# dual_pol_balun_multilayer.net
KiCad netlist of a schematic drawn in EAGLE
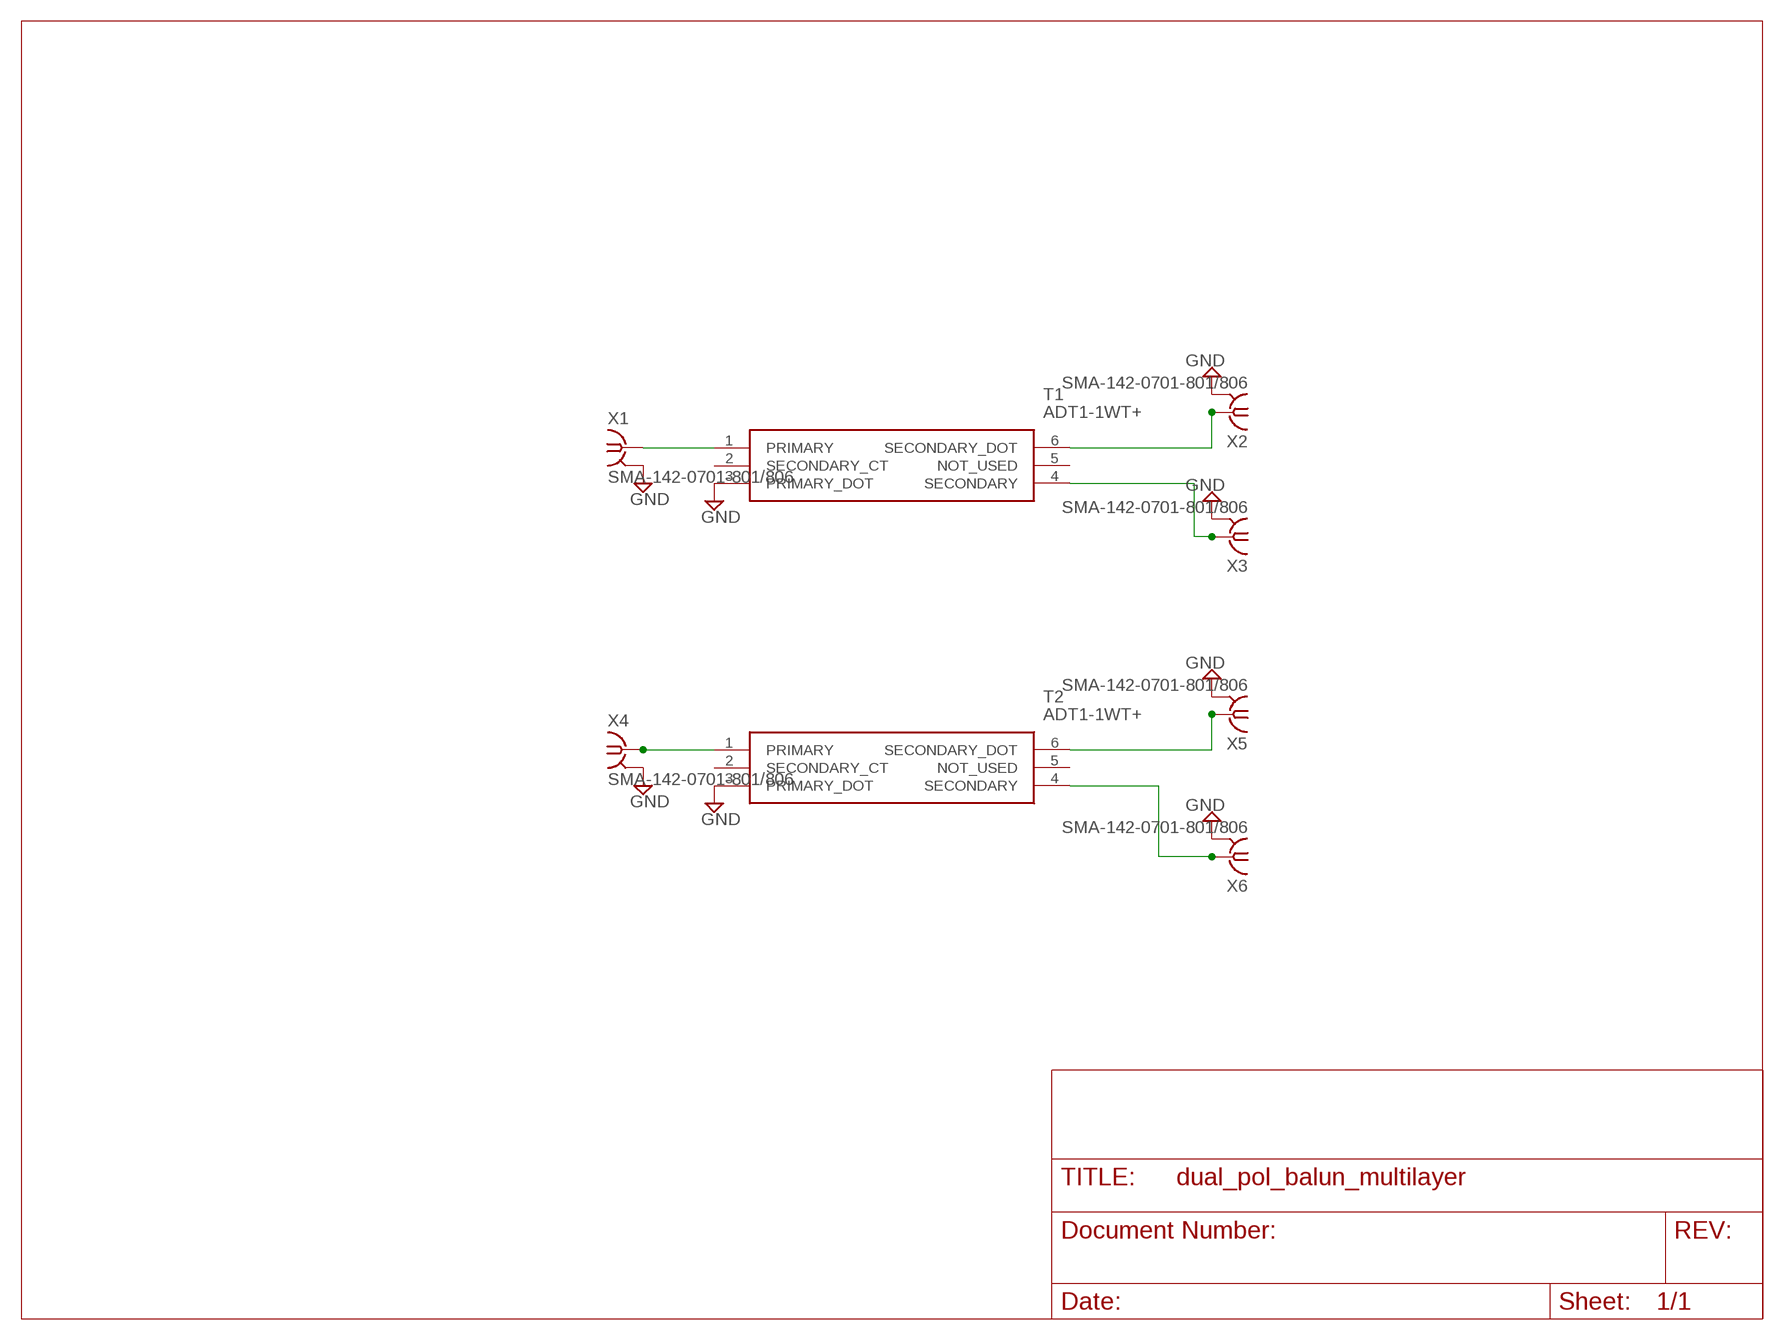
[diagram p0: schematic, sheet 1]

(export (version "E")
  (design (tool "Eeschema 10.0.6"))
  (components
    (comp (ref "T1")
      (value "ADT1-1WT+")
      (footprint "eagle-import:ADT11WT")
      (fields (field (name "MOUSER_PART_NUMBER") "139-ADT1-1WT"))
      (libsource (lib "eagle-import") (part "ADT1-1WT+"))
    )
    (comp (ref "T2")
      (value "ADT1-1WT+")
      (footprint "eagle-import:ADT11WT")
      (fields (field (name "MOUSER_PART_NUMBER") "139-ADT1-1WT"))
      (libsource (lib "eagle-import") (part "ADT1-1WT+"))
    )
    (comp (ref "X1")
      (value "SMA-142-0701-801/806")
      (footprint "eagle-import:J502-ND-142-0701-801_806")
      (fields (field (name "MF") "JOHNSON COMPONENTS") (field (name "MPN") "142-0701-801"))
      (libsource (lib "eagle-import") (part "SMA-142-0701-801/806"))
    )
    (comp (ref "X2")
      (value "SMA-142-0701-801/806")
      (footprint "eagle-import:J502-ND-142-0701-801_806")
      (fields (field (name "MF") "JOHNSON COMPONENTS") (field (name "MPN") "142-0701-801"))
      (libsource (lib "eagle-import") (part "SMA-142-0701-801/806"))
    )
    (comp (ref "X3")
      (value "SMA-142-0701-801/806")
      (footprint "eagle-import:J502-ND-142-0701-801_806")
      (fields (field (name "MF") "JOHNSON COMPONENTS") (field (name "MPN") "142-0701-801"))
      (libsource (lib "eagle-import") (part "SMA-142-0701-801/806"))
    )
    (comp (ref "X4")
      (value "SMA-142-0701-801/806")
      (footprint "eagle-import:J502-ND-142-0701-801_806")
      (fields (field (name "MF") "JOHNSON COMPONENTS") (field (name "MPN") "142-0701-801"))
      (libsource (lib "eagle-import") (part "SMA-142-0701-801/806"))
    )
    (comp (ref "X5")
      (value "SMA-142-0701-801/806")
      (footprint "eagle-import:J502-ND-142-0701-801_806")
      (fields (field (name "MF") "JOHNSON COMPONENTS") (field (name "MPN") "142-0701-801"))
      (libsource (lib "eagle-import") (part "SMA-142-0701-801/806"))
    )
    (comp (ref "X6")
      (value "SMA-142-0701-801/806")
      (footprint "eagle-import:J502-ND-142-0701-801_806")
      (fields (field (name "MF") "JOHNSON COMPONENTS") (field (name "MPN") "142-0701-801"))
      (libsource (lib "eagle-import") (part "SMA-142-0701-801/806"))
    )
  )
  (nets
    (net (code "1") (name "GND") (class "Default")
      (node (ref "T1") (pin "3") (pinfunction "PRIMARY_DOT_3") (pintype "bidirectional"))
      (node (ref "T2") (pin "3") (pinfunction "PRIMARY_DOT_3") (pintype "bidirectional"))
      (node (ref "X1") (pin "G@1") (pinfunction "2_G@1") (pintype "passive"))
      (node (ref "X1") (pin "G@2") (pinfunction "2_G@2") (pintype "passive"))
      (node (ref "X1") (pin "G@3") (pinfunction "2_G@3") (pintype "passive"))
      (node (ref "X1") (pin "G@4") (pinfunction "2_G@4") (pintype "passive"))
      (node (ref "X2") (pin "G@1") (pinfunction "2_G@1") (pintype "passive"))
      (node (ref "X2") (pin "G@2") (pinfunction "2_G@2") (pintype "passive"))
      (node (ref "X2") (pin "G@3") (pinfunction "2_G@3") (pintype "passive"))
      (node (ref "X2") (pin "G@4") (pinfunction "2_G@4") (pintype "passive"))
      (node (ref "X3") (pin "G@1") (pinfunction "2_G@1") (pintype "passive"))
      (node (ref "X3") (pin "G@2") (pinfunction "2_G@2") (pintype "passive"))
      (node (ref "X3") (pin "G@3") (pinfunction "2_G@3") (pintype "passive"))
      (node (ref "X3") (pin "G@4") (pinfunction "2_G@4") (pintype "passive"))
      (node (ref "X4") (pin "G@1") (pinfunction "2_G@1") (pintype "passive"))
      (node (ref "X4") (pin "G@2") (pinfunction "2_G@2") (pintype "passive"))
      (node (ref "X4") (pin "G@3") (pinfunction "2_G@3") (pintype "passive"))
      (node (ref "X4") (pin "G@4") (pinfunction "2_G@4") (pintype "passive"))
      (node (ref "X5") (pin "G@1") (pinfunction "2_G@1") (pintype "passive"))
      (node (ref "X5") (pin "G@2") (pinfunction "2_G@2") (pintype "passive"))
      (node (ref "X5") (pin "G@3") (pinfunction "2_G@3") (pintype "passive"))
      (node (ref "X5") (pin "G@4") (pinfunction "2_G@4") (pintype "passive"))
      (node (ref "X6") (pin "G@1") (pinfunction "2_G@1") (pintype "passive"))
      (node (ref "X6") (pin "G@2") (pinfunction "2_G@2") (pintype "passive"))
      (node (ref "X6") (pin "G@3") (pinfunction "2_G@3") (pintype "passive"))
      (node (ref "X6") (pin "G@4") (pinfunction "2_G@4") (pintype "passive"))
    )
    (net (code "2") (name "Net-(T1-PRIMARY)") (class "Default")
      (node (ref "T1") (pin "1") (pinfunction "PRIMARY_1") (pintype "bidirectional"))
      (node (ref "X1") (pin "1") (pinfunction "1_1") (pintype "passive"))
    )
    (net (code "3") (name "Net-(T1-SECONDARY)") (class "Default")
      (node (ref "T1") (pin "4") (pinfunction "SECONDARY_4") (pintype "bidirectional"))
      (node (ref "X3") (pin "1") (pinfunction "1_1") (pintype "passive"))
    )
    (net (code "4") (name "Net-(T1-SECONDARY_DOT)") (class "Default")
      (node (ref "T1") (pin "6") (pinfunction "SECONDARY_DOT_6") (pintype "bidirectional"))
      (node (ref "X2") (pin "1") (pinfunction "1_1") (pintype "passive"))
    )
    (net (code "5") (name "Net-(T2-PRIMARY)") (class "Default")
      (node (ref "T2") (pin "1") (pinfunction "PRIMARY_1") (pintype "bidirectional"))
      (node (ref "X4") (pin "1") (pinfunction "1_1") (pintype "passive"))
    )
    (net (code "6") (name "Net-(T2-SECONDARY)") (class "Default")
      (node (ref "T2") (pin "4") (pinfunction "SECONDARY_4") (pintype "bidirectional"))
      (node (ref "X6") (pin "1") (pinfunction "1_1") (pintype "passive"))
    )
    (net (code "7") (name "Net-(T2-SECONDARY_DOT)") (class "Default")
      (node (ref "T2") (pin "6") (pinfunction "SECONDARY_DOT_6") (pintype "bidirectional"))
      (node (ref "X5") (pin "1") (pinfunction "1_1") (pintype "passive"))
    )
    (net (code "8") (name "unconnected-(T1-NOT_USED-Pad5)") (class "Default")
      (node (ref "T1") (pin "5") (pinfunction "NOT_USED_5") (pintype "bidirectional"))
    )
    (net (code "9") (name "unconnected-(T1-SECONDARY_CT-Pad2)") (class "Default")
      (node (ref "T1") (pin "2") (pinfunction "SECONDARY_CT_2") (pintype "bidirectional"))
    )
    (net (code "10") (name "unconnected-(T2-NOT_USED-Pad5)") (class "Default")
      (node (ref "T2") (pin "5") (pinfunction "NOT_USED_5") (pintype "bidirectional"))
    )
    (net (code "11") (name "unconnected-(T2-SECONDARY_CT-Pad2)") (class "Default")
      (node (ref "T2") (pin "2") (pinfunction "SECONDARY_CT_2") (pintype "bidirectional"))
    )
  )
)
